# HydrophoneGroup1FilterAndAmpCircuit.net
KiCad netlist of a schematic drawn in Altium Designer
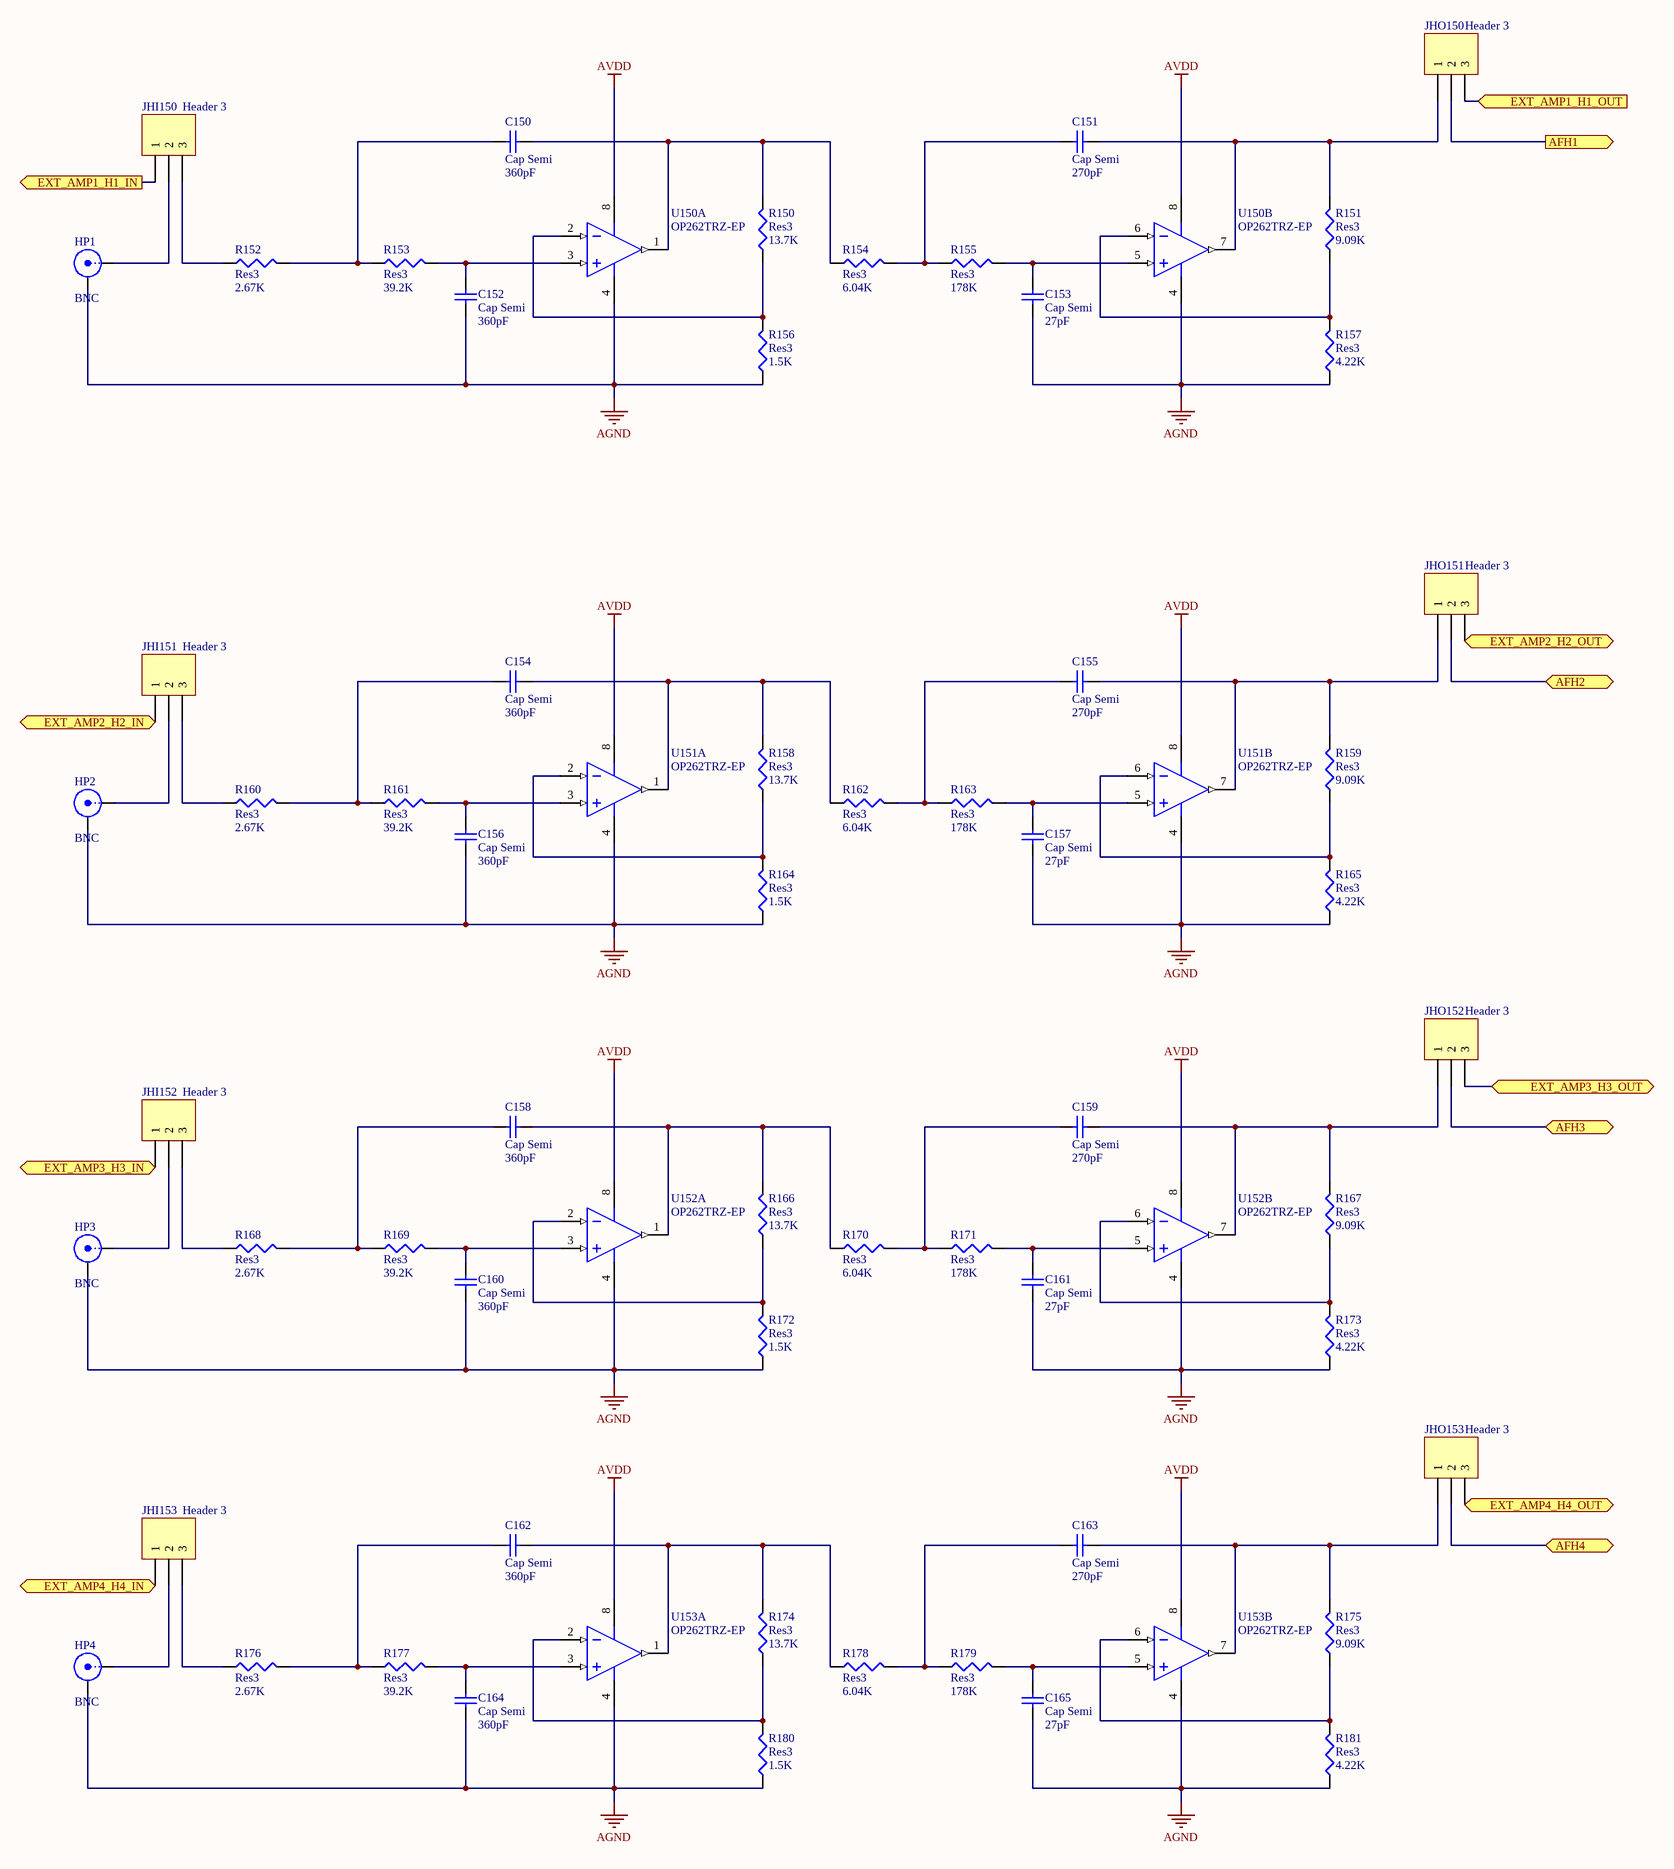
[diagram p0: HydrophoneGroup1FilterAndAmpCircuit.SchDoc]

(export (version "E")
  (design (tool "Eeschema 10.0.6"))
  (components
    (comp (ref "C150")
      (value "Cap Semi")
      (footprint "1608[0603]")
      (description "Capacitor (Semiconductor SIM Model)")
      (fields (field (name "ALTIUM_VALUE") "360pF") (field (name "PUBLISHER") "Altium Limited"))
      (libsource (lib "Miscellaneous Devices") (part "Cap Semi"))
    )
    (comp (ref "C151")
      (value "Cap Semi")
      (footprint "1608[0603]")
      (description "Capacitor (Semiconductor SIM Model)")
      (fields (field (name "ALTIUM_VALUE") "270pF") (field (name "PUBLISHER") "Altium Limited"))
      (libsource (lib "Miscellaneous Devices") (part "Cap Semi"))
    )
    (comp (ref "C152")
      (value "Cap Semi")
      (footprint "1608[0603]")
      (description "Capacitor (Semiconductor SIM Model)")
      (fields (field (name "ALTIUM_VALUE") "360pF") (field (name "PUBLISHER") "Altium Limited"))
      (libsource (lib "Miscellaneous Devices") (part "Cap Semi"))
    )
    (comp (ref "C153")
      (value "Cap Semi")
      (footprint "1608[0603]")
      (description "Capacitor (Semiconductor SIM Model)")
      (fields (field (name "ALTIUM_VALUE") "27pF") (field (name "PUBLISHER") "Altium Limited"))
      (libsource (lib "Miscellaneous Devices") (part "Cap Semi"))
    )
    (comp (ref "C154")
      (value "Cap Semi")
      (footprint "1608[0603]")
      (description "Capacitor (Semiconductor SIM Model)")
      (fields (field (name "ALTIUM_VALUE") "360pF") (field (name "PUBLISHER") "Altium Limited"))
      (libsource (lib "Miscellaneous Devices") (part "Cap Semi"))
    )
    (comp (ref "C155")
      (value "Cap Semi")
      (footprint "1608[0603]")
      (description "Capacitor (Semiconductor SIM Model)")
      (fields (field (name "ALTIUM_VALUE") "270pF") (field (name "PUBLISHER") "Altium Limited"))
      (libsource (lib "Miscellaneous Devices") (part "Cap Semi"))
    )
    (comp (ref "C156")
      (value "Cap Semi")
      (footprint "1608[0603]")
      (description "Capacitor (Semiconductor SIM Model)")
      (fields (field (name "ALTIUM_VALUE") "360pF") (field (name "PUBLISHER") "Altium Limited"))
      (libsource (lib "Miscellaneous Devices") (part "Cap Semi"))
    )
    (comp (ref "C157")
      (value "Cap Semi")
      (footprint "1608[0603]")
      (description "Capacitor (Semiconductor SIM Model)")
      (fields (field (name "ALTIUM_VALUE") "27pF") (field (name "PUBLISHER") "Altium Limited"))
      (libsource (lib "Miscellaneous Devices") (part "Cap Semi"))
    )
    (comp (ref "C158")
      (value "Cap Semi")
      (footprint "1608[0603]")
      (description "Capacitor (Semiconductor SIM Model)")
      (fields (field (name "ALTIUM_VALUE") "360pF") (field (name "PUBLISHER") "Altium Limited"))
      (libsource (lib "Miscellaneous Devices") (part "Cap Semi"))
    )
    (comp (ref "C159")
      (value "Cap Semi")
      (footprint "1608[0603]")
      (description "Capacitor (Semiconductor SIM Model)")
      (fields (field (name "ALTIUM_VALUE") "270pF") (field (name "PUBLISHER") "Altium Limited"))
      (libsource (lib "Miscellaneous Devices") (part "Cap Semi"))
    )
    (comp (ref "C160")
      (value "Cap Semi")
      (footprint "1608[0603]")
      (description "Capacitor (Semiconductor SIM Model)")
      (fields (field (name "ALTIUM_VALUE") "360pF") (field (name "PUBLISHER") "Altium Limited"))
      (libsource (lib "Miscellaneous Devices") (part "Cap Semi"))
    )
    (comp (ref "C161")
      (value "Cap Semi")
      (footprint "1608[0603]")
      (description "Capacitor (Semiconductor SIM Model)")
      (fields (field (name "ALTIUM_VALUE") "27pF") (field (name "PUBLISHER") "Altium Limited"))
      (libsource (lib "Miscellaneous Devices") (part "Cap Semi"))
    )
    (comp (ref "C162")
      (value "Cap Semi")
      (footprint "1608[0603]")
      (description "Capacitor (Semiconductor SIM Model)")
      (fields (field (name "ALTIUM_VALUE") "360pF") (field (name "PUBLISHER") "Altium Limited"))
      (libsource (lib "Miscellaneous Devices") (part "Cap Semi"))
    )
    (comp (ref "C163")
      (value "Cap Semi")
      (footprint "1608[0603]")
      (description "Capacitor (Semiconductor SIM Model)")
      (fields (field (name "ALTIUM_VALUE") "270pF") (field (name "PUBLISHER") "Altium Limited"))
      (libsource (lib "Miscellaneous Devices") (part "Cap Semi"))
    )
    (comp (ref "C164")
      (value "Cap Semi")
      (footprint "1608[0603]")
      (description "Capacitor (Semiconductor SIM Model)")
      (fields (field (name "ALTIUM_VALUE") "360pF") (field (name "PUBLISHER") "Altium Limited"))
      (libsource (lib "Miscellaneous Devices") (part "Cap Semi"))
    )
    (comp (ref "C165")
      (value "Cap Semi")
      (footprint "1608[0603]")
      (description "Capacitor (Semiconductor SIM Model)")
      (fields (field (name "ALTIUM_VALUE") "27pF") (field (name "PUBLISHER") "Altium Limited"))
      (libsource (lib "Miscellaneous Devices") (part "Cap Semi"))
    )
    (comp (ref "HP1")
      (value "BNC")
      (footprint "BNC_RA CON")
      (description "BNC Elbow Connector")
      (fields (field (name "PUBLISHER") "Altium Limited"))
      (libsource (lib "Miscellaneous Connectors") (part "BNC"))
    )
    (comp (ref "HP2")
      (value "BNC")
      (footprint "BNC_RA CON")
      (description "BNC Elbow Connector")
      (fields (field (name "PUBLISHER") "Altium Limited"))
      (libsource (lib "Miscellaneous Connectors") (part "BNC"))
    )
    (comp (ref "HP3")
      (value "BNC")
      (footprint "BNC_RA CON")
      (description "BNC Elbow Connector")
      (fields (field (name "PUBLISHER") "Altium Limited"))
      (libsource (lib "Miscellaneous Connectors") (part "BNC"))
    )
    (comp (ref "HP4")
      (value "BNC")
      (footprint "BNC_RA CON")
      (description "BNC Elbow Connector")
      (fields (field (name "PUBLISHER") "Altium Limited"))
      (libsource (lib "Miscellaneous Connectors") (part "BNC"))
    )
    (comp (ref "JHI150")
      (value "Header 3")
      (footprint "HDR1X3")
      (description "Header, 3-Pin")
      (fields (field (name "PUBLISHER") "Altium Limited"))
      (libsource (lib "Miscellaneous Connectors") (part "Header 3"))
    )
    (comp (ref "JHI151")
      (value "Header 3")
      (footprint "HDR1X3")
      (description "Header, 3-Pin")
      (fields (field (name "PUBLISHER") "Altium Limited"))
      (libsource (lib "Miscellaneous Connectors") (part "Header 3"))
    )
    (comp (ref "JHI152")
      (value "Header 3")
      (footprint "HDR1X3")
      (description "Header, 3-Pin")
      (fields (field (name "PUBLISHER") "Altium Limited"))
      (libsource (lib "Miscellaneous Connectors") (part "Header 3"))
    )
    (comp (ref "JHI153")
      (value "Header 3")
      (footprint "HDR1X3")
      (description "Header, 3-Pin")
      (fields (field (name "PUBLISHER") "Altium Limited"))
      (libsource (lib "Miscellaneous Connectors") (part "Header 3"))
    )
    (comp (ref "JHO150")
      (value "Header 3")
      (footprint "HDR1X3")
      (description "Header, 3-Pin")
      (fields (field (name "PUBLISHER") "Altium Limited"))
      (libsource (lib "Miscellaneous Connectors") (part "Header 3"))
    )
    (comp (ref "JHO151")
      (value "Header 3")
      (footprint "HDR1X3")
      (description "Header, 3-Pin")
      (fields (field (name "PUBLISHER") "Altium Limited"))
      (libsource (lib "Miscellaneous Connectors") (part "Header 3"))
    )
    (comp (ref "JHO152")
      (value "Header 3")
      (footprint "HDR1X3")
      (description "Header, 3-Pin")
      (fields (field (name "PUBLISHER") "Altium Limited"))
      (libsource (lib "Miscellaneous Connectors") (part "Header 3"))
    )
    (comp (ref "JHO153")
      (value "Header 3")
      (footprint "HDR1X3")
      (description "Header, 3-Pin")
      (fields (field (name "PUBLISHER") "Altium Limited"))
      (libsource (lib "Miscellaneous Connectors") (part "Header 3"))
    )
    (comp (ref "R150")
      (value "Res3")
      (footprint "J1-0603")
      (description "Resistor")
      (fields (field (name "ALTIUM_VALUE") "13.7K") (field (name "PUBLISHER") "Altium Limited"))
      (libsource (lib "Miscellaneous Devices") (part "Res3"))
    )
    (comp (ref "R151")
      (value "Res3")
      (footprint "J1-0603")
      (description "Resistor")
      (fields (field (name "ALTIUM_VALUE") "9.09K") (field (name "PUBLISHER") "Altium Limited"))
      (libsource (lib "Miscellaneous Devices") (part "Res3"))
    )
    (comp (ref "R152")
      (value "Res3")
      (footprint "J1-0603")
      (description "Resistor")
      (fields (field (name "ALTIUM_VALUE") "2.67K") (field (name "PUBLISHER") "Altium Limited"))
      (libsource (lib "Miscellaneous Devices") (part "Res3"))
    )
    (comp (ref "R153")
      (value "Res3")
      (footprint "J1-0603")
      (description "Resistor")
      (fields (field (name "ALTIUM_VALUE") "39.2K") (field (name "PUBLISHER") "Altium Limited"))
      (libsource (lib "Miscellaneous Devices") (part "Res3"))
    )
    (comp (ref "R154")
      (value "Res3")
      (footprint "J1-0603")
      (description "Resistor")
      (fields (field (name "ALTIUM_VALUE") "6.04K") (field (name "PUBLISHER") "Altium Limited"))
      (libsource (lib "Miscellaneous Devices") (part "Res3"))
    )
    (comp (ref "R155")
      (value "Res3")
      (footprint "J1-0603")
      (description "Resistor")
      (fields (field (name "ALTIUM_VALUE") "178K") (field (name "PUBLISHER") "Altium Limited"))
      (libsource (lib "Miscellaneous Devices") (part "Res3"))
    )
    (comp (ref "R156")
      (value "Res3")
      (footprint "J1-0603")
      (description "Resistor")
      (fields (field (name "ALTIUM_VALUE") "1.5K") (field (name "PUBLISHER") "Altium Limited"))
      (libsource (lib "Miscellaneous Devices") (part "Res3"))
    )
    (comp (ref "R157")
      (value "Res3")
      (footprint "J1-0603")
      (description "Resistor")
      (fields (field (name "ALTIUM_VALUE") "4.22K") (field (name "PUBLISHER") "Altium Limited"))
      (libsource (lib "Miscellaneous Devices") (part "Res3"))
    )
    (comp (ref "R158")
      (value "Res3")
      (footprint "J1-0603")
      (description "Resistor")
      (fields (field (name "ALTIUM_VALUE") "13.7K") (field (name "PUBLISHER") "Altium Limited"))
      (libsource (lib "Miscellaneous Devices") (part "Res3"))
    )
    (comp (ref "R159")
      (value "Res3")
      (footprint "J1-0603")
      (description "Resistor")
      (fields (field (name "ALTIUM_VALUE") "9.09K") (field (name "PUBLISHER") "Altium Limited"))
      (libsource (lib "Miscellaneous Devices") (part "Res3"))
    )
    (comp (ref "R160")
      (value "Res3")
      (footprint "J1-0603")
      (description "Resistor")
      (fields (field (name "ALTIUM_VALUE") "2.67K") (field (name "PUBLISHER") "Altium Limited"))
      (libsource (lib "Miscellaneous Devices") (part "Res3"))
    )
    (comp (ref "R161")
      (value "Res3")
      (footprint "J1-0603")
      (description "Resistor")
      (fields (field (name "ALTIUM_VALUE") "39.2K") (field (name "PUBLISHER") "Altium Limited"))
      (libsource (lib "Miscellaneous Devices") (part "Res3"))
    )
    (comp (ref "R162")
      (value "Res3")
      (footprint "J1-0603")
      (description "Resistor")
      (fields (field (name "ALTIUM_VALUE") "6.04K") (field (name "PUBLISHER") "Altium Limited"))
      (libsource (lib "Miscellaneous Devices") (part "Res3"))
    )
    (comp (ref "R163")
      (value "Res3")
      (footprint "J1-0603")
      (description "Resistor")
      (fields (field (name "ALTIUM_VALUE") "178K") (field (name "PUBLISHER") "Altium Limited"))
      (libsource (lib "Miscellaneous Devices") (part "Res3"))
    )
    (comp (ref "R164")
      (value "Res3")
      (footprint "J1-0603")
      (description "Resistor")
      (fields (field (name "ALTIUM_VALUE") "1.5K") (field (name "PUBLISHER") "Altium Limited"))
      (libsource (lib "Miscellaneous Devices") (part "Res3"))
    )
    (comp (ref "R165")
      (value "Res3")
      (footprint "J1-0603")
      (description "Resistor")
      (fields (field (name "ALTIUM_VALUE") "4.22K") (field (name "PUBLISHER") "Altium Limited"))
      (libsource (lib "Miscellaneous Devices") (part "Res3"))
    )
    (comp (ref "R166")
      (value "Res3")
      (footprint "J1-0603")
      (description "Resistor")
      (fields (field (name "ALTIUM_VALUE") "13.7K") (field (name "PUBLISHER") "Altium Limited"))
      (libsource (lib "Miscellaneous Devices") (part "Res3"))
    )
    (comp (ref "R167")
      (value "Res3")
      (footprint "J1-0603")
      (description "Resistor")
      (fields (field (name "ALTIUM_VALUE") "9.09K") (field (name "PUBLISHER") "Altium Limited"))
      (libsource (lib "Miscellaneous Devices") (part "Res3"))
    )
    (comp (ref "R168")
      (value "Res3")
      (footprint "J1-0603")
      (description "Resistor")
      (fields (field (name "ALTIUM_VALUE") "2.67K") (field (name "PUBLISHER") "Altium Limited"))
      (libsource (lib "Miscellaneous Devices") (part "Res3"))
    )
    (comp (ref "R169")
      (value "Res3")
      (footprint "J1-0603")
      (description "Resistor")
      (fields (field (name "ALTIUM_VALUE") "39.2K") (field (name "PUBLISHER") "Altium Limited"))
      (libsource (lib "Miscellaneous Devices") (part "Res3"))
    )
    (comp (ref "R170")
      (value "Res3")
      (footprint "J1-0603")
      (description "Resistor")
      (fields (field (name "ALTIUM_VALUE") "6.04K") (field (name "PUBLISHER") "Altium Limited"))
      (libsource (lib "Miscellaneous Devices") (part "Res3"))
    )
    (comp (ref "R171")
      (value "Res3")
      (footprint "J1-0603")
      (description "Resistor")
      (fields (field (name "ALTIUM_VALUE") "178K") (field (name "PUBLISHER") "Altium Limited"))
      (libsource (lib "Miscellaneous Devices") (part "Res3"))
    )
    (comp (ref "R172")
      (value "Res3")
      (footprint "J1-0603")
      (description "Resistor")
      (fields (field (name "ALTIUM_VALUE") "1.5K") (field (name "PUBLISHER") "Altium Limited"))
      (libsource (lib "Miscellaneous Devices") (part "Res3"))
    )
    (comp (ref "R173")
      (value "Res3")
      (footprint "J1-0603")
      (description "Resistor")
      (fields (field (name "ALTIUM_VALUE") "4.22K") (field (name "PUBLISHER") "Altium Limited"))
      (libsource (lib "Miscellaneous Devices") (part "Res3"))
    )
    (comp (ref "R174")
      (value "Res3")
      (footprint "J1-0603")
      (description "Resistor")
      (fields (field (name "ALTIUM_VALUE") "13.7K") (field (name "PUBLISHER") "Altium Limited"))
      (libsource (lib "Miscellaneous Devices") (part "Res3"))
    )
    (comp (ref "R175")
      (value "Res3")
      (footprint "J1-0603")
      (description "Resistor")
      (fields (field (name "ALTIUM_VALUE") "9.09K") (field (name "PUBLISHER") "Altium Limited"))
      (libsource (lib "Miscellaneous Devices") (part "Res3"))
    )
    (comp (ref "R176")
      (value "Res3")
      (footprint "J1-0603")
      (description "Resistor")
      (fields (field (name "ALTIUM_VALUE") "2.67K") (field (name "PUBLISHER") "Altium Limited"))
      (libsource (lib "Miscellaneous Devices") (part "Res3"))
    )
    (comp (ref "R177")
      (value "Res3")
      (footprint "J1-0603")
      (description "Resistor")
      (fields (field (name "ALTIUM_VALUE") "39.2K") (field (name "PUBLISHER") "Altium Limited"))
      (libsource (lib "Miscellaneous Devices") (part "Res3"))
    )
    (comp (ref "R178")
      (value "Res3")
      (footprint "J1-0603")
      (description "Resistor")
      (fields (field (name "ALTIUM_VALUE") "6.04K") (field (name "PUBLISHER") "Altium Limited"))
      (libsource (lib "Miscellaneous Devices") (part "Res3"))
    )
    (comp (ref "R179")
      (value "Res3")
      (footprint "J1-0603")
      (description "Resistor")
      (fields (field (name "ALTIUM_VALUE") "178K") (field (name "PUBLISHER") "Altium Limited"))
      (libsource (lib "Miscellaneous Devices") (part "Res3"))
    )
    (comp (ref "R180")
      (value "Res3")
      (footprint "J1-0603")
      (description "Resistor")
      (fields (field (name "ALTIUM_VALUE") "1.5K") (field (name "PUBLISHER") "Altium Limited"))
      (libsource (lib "Miscellaneous Devices") (part "Res3"))
    )
    (comp (ref "R181")
      (value "Res3")
      (footprint "J1-0603")
      (description "Resistor")
      (fields (field (name "ALTIUM_VALUE") "4.22K") (field (name "PUBLISHER") "Altium Limited"))
      (libsource (lib "Miscellaneous Devices") (part "Res3"))
    )
    (comp (ref "U150")
      (value "OP262TRZ-EP")
      (footprint "ADI-R-8_N")
      (fields (field (name "GENERIC PART NUMBER") "OP262") (field (name "MANUFACTURER") "Analog Devices"))
      (libsource (lib "Analog Devices Operational Amplifiers") (part "OP262TRZ-EP"))
    )
    (comp (ref "U151")
      (value "OP262TRZ-EP")
      (footprint "ADI-R-8_N")
      (fields (field (name "GENERIC PART NUMBER") "OP262") (field (name "MANUFACTURER") "Analog Devices"))
      (libsource (lib "Analog Devices Operational Amplifiers") (part "OP262TRZ-EP"))
    )
    (comp (ref "U152")
      (value "OP262TRZ-EP")
      (footprint "ADI-R-8_N")
      (fields (field (name "GENERIC PART NUMBER") "OP262") (field (name "MANUFACTURER") "Analog Devices"))
      (libsource (lib "Analog Devices Operational Amplifiers") (part "OP262TRZ-EP"))
    )
    (comp (ref "U153")
      (value "OP262TRZ-EP")
      (footprint "ADI-R-8_N")
      (fields (field (name "GENERIC PART NUMBER") "OP262") (field (name "MANUFACTURER") "Analog Devices"))
      (libsource (lib "Analog Devices Operational Amplifiers") (part "OP262TRZ-EP"))
    )
  )
  (nets
    (net (code "1") (name "/AFH1") (class "Default")
      (node (ref "JHO150") (pin "2") (pinfunction "2_2") (pintype "passive"))
    )
    (net (code "2") (name "/AFH2") (class "Default")
      (node (ref "JHO151") (pin "2") (pinfunction "2_2") (pintype "passive"))
    )
    (net (code "3") (name "/AFH3") (class "Default")
      (node (ref "JHO152") (pin "2") (pinfunction "2_2") (pintype "passive"))
    )
    (net (code "4") (name "/AFH4") (class "Default")
      (node (ref "JHO153") (pin "2") (pinfunction "2_2") (pintype "passive"))
    )
    (net (code "5") (name "/EXT_AMP1_H1_IN") (class "Default")
      (node (ref "JHI150") (pin "1") (pinfunction "1_1") (pintype "passive"))
    )
    (net (code "6") (name "/EXT_AMP1_H1_OUT") (class "Default")
      (node (ref "JHO150") (pin "3") (pinfunction "3_3") (pintype "passive"))
    )
    (net (code "7") (name "/EXT_AMP2_H2_IN") (class "Default")
      (node (ref "JHI151") (pin "1") (pinfunction "1_1") (pintype "passive"))
    )
    (net (code "8") (name "/EXT_AMP2_H2_OUT") (class "Default")
      (node (ref "JHO151") (pin "3") (pinfunction "3_3") (pintype "passive"))
    )
    (net (code "9") (name "/EXT_AMP3_H3_IN") (class "Default")
      (node (ref "JHI152") (pin "1") (pinfunction "1_1") (pintype "passive"))
    )
    (net (code "10") (name "/EXT_AMP3_H3_OUT") (class "Default")
      (node (ref "JHO152") (pin "3") (pinfunction "3_3") (pintype "passive"))
    )
    (net (code "11") (name "/EXT_AMP4_H4_IN") (class "Default")
      (node (ref "JHI153") (pin "1") (pinfunction "1_1") (pintype "passive"))
    )
    (net (code "12") (name "/EXT_AMP4_H4_OUT") (class "Default")
      (node (ref "JHO153") (pin "3") (pinfunction "3_3") (pintype "passive"))
    )
    (net (code "13") (name "AGND") (class "Default")
      (node (ref "C152") (pin "1") (pinfunction "1_1") (pintype "passive"))
      (node (ref "C153") (pin "1") (pinfunction "1_1") (pintype "passive"))
      (node (ref "C156") (pin "1") (pinfunction "1_1") (pintype "passive"))
      (node (ref "C157") (pin "1") (pinfunction "1_1") (pintype "passive"))
      (node (ref "C160") (pin "1") (pinfunction "1_1") (pintype "passive"))
      (node (ref "C161") (pin "1") (pinfunction "1_1") (pintype "passive"))
      (node (ref "C164") (pin "1") (pinfunction "1_1") (pintype "passive"))
      (node (ref "C165") (pin "1") (pinfunction "1_1") (pintype "passive"))
      (node (ref "HP1") (pin "2") (pinfunction "Y_2") (pintype "passive"))
      (node (ref "HP2") (pin "2") (pinfunction "Y_2") (pintype "passive"))
      (node (ref "HP3") (pin "2") (pinfunction "Y_2") (pintype "passive"))
      (node (ref "HP4") (pin "2") (pinfunction "Y_2") (pintype "passive"))
      (node (ref "R156") (pin "1") (pinfunction "1_1") (pintype "passive"))
      (node (ref "R157") (pin "1") (pinfunction "1_1") (pintype "passive"))
      (node (ref "R164") (pin "1") (pinfunction "1_1") (pintype "passive"))
      (node (ref "R165") (pin "1") (pinfunction "1_1") (pintype "passive"))
      (node (ref "R172") (pin "1") (pinfunction "1_1") (pintype "passive"))
      (node (ref "R173") (pin "1") (pinfunction "1_1") (pintype "passive"))
      (node (ref "R180") (pin "1") (pinfunction "1_1") (pintype "passive"))
      (node (ref "R181") (pin "1") (pinfunction "1_1") (pintype "passive"))
      (node (ref "U150") (pin "4") (pinfunction "-V_4") (pintype "power_in"))
      (node (ref "U151") (pin "4") (pinfunction "-V_4") (pintype "power_in"))
      (node (ref "U152") (pin "4") (pinfunction "-V_4") (pintype "power_in"))
      (node (ref "U153") (pin "4") (pinfunction "-V_4") (pintype "power_in"))
    )
    (net (code "14") (name "AVDD") (class "Default")
      (node (ref "U150") (pin "8") (pinfunction "+V_8") (pintype "power_in"))
      (node (ref "U151") (pin "8") (pinfunction "+V_8") (pintype "power_in"))
      (node (ref "U152") (pin "8") (pinfunction "+V_8") (pintype "power_in"))
      (node (ref "U153") (pin "8") (pinfunction "+V_8") (pintype "power_in"))
    )
    (net (code "15") (name "Net-(C150-Pad1)") (class "Default")
      (node (ref "C150") (pin "1") (pinfunction "1_1") (pintype "passive"))
      (node (ref "R152") (pin "2") (pinfunction "2_2") (pintype "passive"))
      (node (ref "R153") (pin "1") (pinfunction "1_1") (pintype "passive"))
    )
    (net (code "16") (name "Net-(C151-Pad1)") (class "Default")
      (node (ref "C151") (pin "1") (pinfunction "1_1") (pintype "passive"))
      (node (ref "R154") (pin "2") (pinfunction "2_2") (pintype "passive"))
      (node (ref "R155") (pin "1") (pinfunction "1_1") (pintype "passive"))
    )
    (net (code "17") (name "Net-(C154-Pad1)") (class "Default")
      (node (ref "C154") (pin "1") (pinfunction "1_1") (pintype "passive"))
      (node (ref "R160") (pin "2") (pinfunction "2_2") (pintype "passive"))
      (node (ref "R161") (pin "1") (pinfunction "1_1") (pintype "passive"))
    )
    (net (code "18") (name "Net-(C155-Pad1)") (class "Default")
      (node (ref "C155") (pin "1") (pinfunction "1_1") (pintype "passive"))
      (node (ref "R162") (pin "2") (pinfunction "2_2") (pintype "passive"))
      (node (ref "R163") (pin "1") (pinfunction "1_1") (pintype "passive"))
    )
    (net (code "19") (name "Net-(C158-Pad1)") (class "Default")
      (node (ref "C158") (pin "1") (pinfunction "1_1") (pintype "passive"))
      (node (ref "R168") (pin "2") (pinfunction "2_2") (pintype "passive"))
      (node (ref "R169") (pin "1") (pinfunction "1_1") (pintype "passive"))
    )
    (net (code "20") (name "Net-(C159-Pad1)") (class "Default")
      (node (ref "C159") (pin "1") (pinfunction "1_1") (pintype "passive"))
      (node (ref "R170") (pin "2") (pinfunction "2_2") (pintype "passive"))
      (node (ref "R171") (pin "1") (pinfunction "1_1") (pintype "passive"))
    )
    (net (code "21") (name "Net-(C162-Pad1)") (class "Default")
      (node (ref "C162") (pin "1") (pinfunction "1_1") (pintype "passive"))
      (node (ref "R176") (pin "2") (pinfunction "2_2") (pintype "passive"))
      (node (ref "R177") (pin "1") (pinfunction "1_1") (pintype "passive"))
    )
    (net (code "22") (name "Net-(C163-Pad1)") (class "Default")
      (node (ref "C163") (pin "1") (pinfunction "1_1") (pintype "passive"))
      (node (ref "R178") (pin "2") (pinfunction "2_2") (pintype "passive"))
      (node (ref "R179") (pin "1") (pinfunction "1_1") (pintype "passive"))
    )
    (net (code "23") (name "Net-(HP1-X)") (class "Default")
      (node (ref "HP1") (pin "1") (pinfunction "X_1") (pintype "passive"))
      (node (ref "JHI150") (pin "2") (pinfunction "2_2") (pintype "passive"))
    )
    (net (code "24") (name "Net-(HP2-X)") (class "Default")
      (node (ref "HP2") (pin "1") (pinfunction "X_1") (pintype "passive"))
      (node (ref "JHI151") (pin "2") (pinfunction "2_2") (pintype "passive"))
    )
    (net (code "25") (name "Net-(HP3-X)") (class "Default")
      (node (ref "HP3") (pin "1") (pinfunction "X_1") (pintype "passive"))
      (node (ref "JHI152") (pin "2") (pinfunction "2_2") (pintype "passive"))
    )
    (net (code "26") (name "Net-(HP4-X)") (class "Default")
      (node (ref "HP4") (pin "1") (pinfunction "X_1") (pintype "passive"))
      (node (ref "JHI153") (pin "2") (pinfunction "2_2") (pintype "passive"))
    )
    (net (code "27") (name "Net-(JHI150-Pad3)") (class "Default")
      (node (ref "JHI150") (pin "3") (pinfunction "3_3") (pintype "passive"))
      (node (ref "R152") (pin "1") (pinfunction "1_1") (pintype "passive"))
    )
    (net (code "28") (name "Net-(JHI151-Pad3)") (class "Default")
      (node (ref "JHI151") (pin "3") (pinfunction "3_3") (pintype "passive"))
      (node (ref "R160") (pin "1") (pinfunction "1_1") (pintype "passive"))
    )
    (net (code "29") (name "Net-(JHI152-Pad3)") (class "Default")
      (node (ref "JHI152") (pin "3") (pinfunction "3_3") (pintype "passive"))
      (node (ref "R168") (pin "1") (pinfunction "1_1") (pintype "passive"))
    )
    (net (code "30") (name "Net-(JHI153-Pad3)") (class "Default")
      (node (ref "JHI153") (pin "3") (pinfunction "3_3") (pintype "passive"))
      (node (ref "R176") (pin "1") (pinfunction "1_1") (pintype "passive"))
    )
    (net (code "31") (name "Net-(U150A-+IN_A)") (class "Default")
      (node (ref "C152") (pin "2") (pinfunction "2_2") (pintype "passive"))
      (node (ref "R153") (pin "2") (pinfunction "2_2") (pintype "passive"))
      (node (ref "U150") (pin "3") (pinfunction "+IN_A_3") (pintype "input"))
    )
    (net (code "32") (name "Net-(U150A--IN_A)") (class "Default")
      (node (ref "R150") (pin "1") (pinfunction "1_1") (pintype "passive"))
      (node (ref "R156") (pin "2") (pinfunction "2_2") (pintype "passive"))
      (node (ref "U150") (pin "2") (pinfunction "-IN_A_2") (pintype "input"))
    )
    (net (code "33") (name "Net-(U150A-OUT_A)") (class "Default")
      (node (ref "C150") (pin "2") (pinfunction "2_2") (pintype "passive"))
      (node (ref "R150") (pin "2") (pinfunction "2_2") (pintype "passive"))
      (node (ref "R154") (pin "1") (pinfunction "1_1") (pintype "passive"))
      (node (ref "U150") (pin "1") (pinfunction "OUT_A_1") (pintype "output"))
    )
    (net (code "34") (name "Net-(U150B-+IN_B)") (class "Default")
      (node (ref "C153") (pin "2") (pinfunction "2_2") (pintype "passive"))
      (node (ref "R155") (pin "2") (pinfunction "2_2") (pintype "passive"))
      (node (ref "U150") (pin "5") (pinfunction "+IN_B_5") (pintype "input"))
    )
    (net (code "35") (name "Net-(U150B--IN_B)") (class "Default")
      (node (ref "R151") (pin "1") (pinfunction "1_1") (pintype "passive"))
      (node (ref "R157") (pin "2") (pinfunction "2_2") (pintype "passive"))
      (node (ref "U150") (pin "6") (pinfunction "-IN_B_6") (pintype "input"))
    )
    (net (code "36") (name "Net-(U150B-OUT_B)") (class "Default")
      (node (ref "C151") (pin "2") (pinfunction "2_2") (pintype "passive"))
      (node (ref "JHO150") (pin "1") (pinfunction "1_1") (pintype "passive"))
      (node (ref "R151") (pin "2") (pinfunction "2_2") (pintype "passive"))
      (node (ref "U150") (pin "7") (pinfunction "OUT_B_7") (pintype "output"))
    )
    (net (code "37") (name "Net-(U151A-+IN_A)") (class "Default")
      (node (ref "C156") (pin "2") (pinfunction "2_2") (pintype "passive"))
      (node (ref "R161") (pin "2") (pinfunction "2_2") (pintype "passive"))
      (node (ref "U151") (pin "3") (pinfunction "+IN_A_3") (pintype "input"))
    )
    (net (code "38") (name "Net-(U151A--IN_A)") (class "Default")
      (node (ref "R158") (pin "1") (pinfunction "1_1") (pintype "passive"))
      (node (ref "R164") (pin "2") (pinfunction "2_2") (pintype "passive"))
      (node (ref "U151") (pin "2") (pinfunction "-IN_A_2") (pintype "input"))
    )
    (net (code "39") (name "Net-(U151A-OUT_A)") (class "Default")
      (node (ref "C154") (pin "2") (pinfunction "2_2") (pintype "passive"))
      (node (ref "R158") (pin "2") (pinfunction "2_2") (pintype "passive"))
      (node (ref "R162") (pin "1") (pinfunction "1_1") (pintype "passive"))
      (node (ref "U151") (pin "1") (pinfunction "OUT_A_1") (pintype "output"))
    )
    (net (code "40") (name "Net-(U151B-+IN_B)") (class "Default")
      (node (ref "C157") (pin "2") (pinfunction "2_2") (pintype "passive"))
      (node (ref "R163") (pin "2") (pinfunction "2_2") (pintype "passive"))
      (node (ref "U151") (pin "5") (pinfunction "+IN_B_5") (pintype "input"))
    )
    (net (code "41") (name "Net-(U151B--IN_B)") (class "Default")
      (node (ref "R159") (pin "1") (pinfunction "1_1") (pintype "passive"))
      (node (ref "R165") (pin "2") (pinfunction "2_2") (pintype "passive"))
      (node (ref "U151") (pin "6") (pinfunction "-IN_B_6") (pintype "input"))
    )
    (net (code "42") (name "Net-(U151B-OUT_B)") (class "Default")
      (node (ref "C155") (pin "2") (pinfunction "2_2") (pintype "passive"))
      (node (ref "JHO151") (pin "1") (pinfunction "1_1") (pintype "passive"))
      (node (ref "R159") (pin "2") (pinfunction "2_2") (pintype "passive"))
      (node (ref "U151") (pin "7") (pinfunction "OUT_B_7") (pintype "output"))
    )
    (net (code "43") (name "Net-(U152A-+IN_A)") (class "Default")
      (node (ref "C160") (pin "2") (pinfunction "2_2") (pintype "passive"))
      (node (ref "R169") (pin "2") (pinfunction "2_2") (pintype "passive"))
      (node (ref "U152") (pin "3") (pinfunction "+IN_A_3") (pintype "input"))
    )
    (net (code "44") (name "Net-(U152A--IN_A)") (class "Default")
      (node (ref "R166") (pin "1") (pinfunction "1_1") (pintype "passive"))
      (node (ref "R172") (pin "2") (pinfunction "2_2") (pintype "passive"))
      (node (ref "U152") (pin "2") (pinfunction "-IN_A_2") (pintype "input"))
    )
    (net (code "45") (name "Net-(U152A-OUT_A)") (class "Default")
      (node (ref "C158") (pin "2") (pinfunction "2_2") (pintype "passive"))
      (node (ref "R166") (pin "2") (pinfunction "2_2") (pintype "passive"))
      (node (ref "R170") (pin "1") (pinfunction "1_1") (pintype "passive"))
      (node (ref "U152") (pin "1") (pinfunction "OUT_A_1") (pintype "output"))
    )
    (net (code "46") (name "Net-(U152B-+IN_B)") (class "Default")
      (node (ref "C161") (pin "2") (pinfunction "2_2") (pintype "passive"))
      (node (ref "R171") (pin "2") (pinfunction "2_2") (pintype "passive"))
      (node (ref "U152") (pin "5") (pinfunction "+IN_B_5") (pintype "input"))
    )
    (net (code "47") (name "Net-(U152B--IN_B)") (class "Default")
      (node (ref "R167") (pin "1") (pinfunction "1_1") (pintype "passive"))
      (node (ref "R173") (pin "2") (pinfunction "2_2") (pintype "passive"))
      (node (ref "U152") (pin "6") (pinfunction "-IN_B_6") (pintype "input"))
    )
    (net (code "48") (name "Net-(U152B-OUT_B)") (class "Default")
      (node (ref "C159") (pin "2") (pinfunction "2_2") (pintype "passive"))
      (node (ref "JHO152") (pin "1") (pinfunction "1_1") (pintype "passive"))
      (node (ref "R167") (pin "2") (pinfunction "2_2") (pintype "passive"))
      (node (ref "U152") (pin "7") (pinfunction "OUT_B_7") (pintype "output"))
    )
    (net (code "49") (name "Net-(U153A-+IN_A)") (class "Default")
      (node (ref "C164") (pin "2") (pinfunction "2_2") (pintype "passive"))
      (node (ref "R177") (pin "2") (pinfunction "2_2") (pintype "passive"))
      (node (ref "U153") (pin "3") (pinfunction "+IN_A_3") (pintype "input"))
    )
    (net (code "50") (name "Net-(U153A--IN_A)") (class "Default")
      (node (ref "R174") (pin "1") (pinfunction "1_1") (pintype "passive"))
      (node (ref "R180") (pin "2") (pinfunction "2_2") (pintype "passive"))
      (node (ref "U153") (pin "2") (pinfunction "-IN_A_2") (pintype "input"))
    )
    (net (code "51") (name "Net-(U153A-OUT_A)") (class "Default")
      (node (ref "C162") (pin "2") (pinfunction "2_2") (pintype "passive"))
      (node (ref "R174") (pin "2") (pinfunction "2_2") (pintype "passive"))
      (node (ref "R178") (pin "1") (pinfunction "1_1") (pintype "passive"))
      (node (ref "U153") (pin "1") (pinfunction "OUT_A_1") (pintype "output"))
    )
    (net (code "52") (name "Net-(U153B-+IN_B)") (class "Default")
      (node (ref "C165") (pin "2") (pinfunction "2_2") (pintype "passive"))
      (node (ref "R179") (pin "2") (pinfunction "2_2") (pintype "passive"))
      (node (ref "U153") (pin "5") (pinfunction "+IN_B_5") (pintype "input"))
    )
    (net (code "53") (name "Net-(U153B--IN_B)") (class "Default")
      (node (ref "R175") (pin "1") (pinfunction "1_1") (pintype "passive"))
      (node (ref "R181") (pin "2") (pinfunction "2_2") (pintype "passive"))
      (node (ref "U153") (pin "6") (pinfunction "-IN_B_6") (pintype "input"))
    )
    (net (code "54") (name "Net-(U153B-OUT_B)") (class "Default")
      (node (ref "C163") (pin "2") (pinfunction "2_2") (pintype "passive"))
      (node (ref "JHO153") (pin "1") (pinfunction "1_1") (pintype "passive"))
      (node (ref "R175") (pin "2") (pinfunction "2_2") (pintype "passive"))
      (node (ref "U153") (pin "7") (pinfunction "OUT_B_7") (pintype "output"))
    )
  )
)
